# Motordrive.net
KiCad netlist of a schematic drawn in Altium Designer
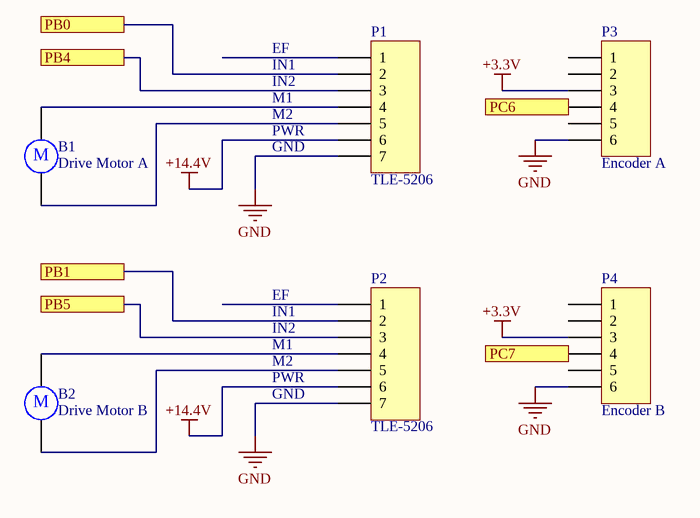
[diagram p0: Motordrive.SchDoc]

(export (version "E")
  (design (tool "Eeschema 10.0.6"))
  (components
    (comp (ref "B1")
      (value "Drive Motor A")
      (footprint "RB5-10.5")
      (description "Motor, General Kind")
      (fields (field (name "MANUFACTURER") "Generic Components"))
      (libsource (lib "ME218_BaseLib") (part "Motor"))
    )
    (comp (ref "B2")
      (value "Drive Motor B")
      (footprint "RB5-10.5")
      (description "Motor, General Kind")
      (fields (field (name "MANUFACTURER") "Generic Components"))
      (libsource (lib "ME218_BaseLib") (part "Motor"))
    )
    (comp (ref "P1")
      (value "TLE-5206")
      (footprint "HDR1X7")
      (description "Header, 7-Pin")
      (fields (field (name "PUBLISHER") "Altium Limited"))
      (libsource (lib "Miscellaneous Connectors") (part "Header 7"))
    )
    (comp (ref "P2")
      (value "TLE-5206")
      (footprint "HDR1X7")
      (description "Header, 7-Pin")
      (fields (field (name "PUBLISHER") "Altium Limited"))
      (libsource (lib "Miscellaneous Connectors") (part "Header 7"))
    )
    (comp (ref "P3")
      (value "Encoder A")
      (footprint "HDR1X6")
      (description "Header, 6-Pin")
      (fields (field (name "PUBLISHER") "Altium Limited"))
      (libsource (lib "Miscellaneous Connectors") (part "Header 6"))
    )
    (comp (ref "P4")
      (value "Encoder B")
      (footprint "HDR1X6")
      (description "Header, 6-Pin")
      (fields (field (name "PUBLISHER") "Altium Limited"))
      (libsource (lib "Miscellaneous Connectors") (part "Header 6"))
    )
  )
  (nets
    (net (code "1") (name "+3.3V") (class "Default")
      (node (ref "P3") (pin "3") (pinfunction "3_3") (pintype "passive"))
      (node (ref "P4") (pin "3") (pinfunction "3_3") (pintype "passive"))
    )
    (net (code "2") (name "+14.4V") (class "Default")
      (node (ref "P1") (pin "6") (pinfunction "6_6") (pintype "passive"))
      (node (ref "P2") (pin "6") (pinfunction "6_6") (pintype "passive"))
    )
    (net (code "3") (name "/PB0") (class "Default")
      (node (ref "P1") (pin "2") (pinfunction "2_2") (pintype "passive"))
    )
    (net (code "4") (name "/PB1") (class "Default")
      (node (ref "P2") (pin "2") (pinfunction "2_2") (pintype "passive"))
    )
    (net (code "5") (name "/PB4") (class "Default")
      (node (ref "P1") (pin "3") (pinfunction "3_3") (pintype "passive"))
    )
    (net (code "6") (name "/PB5") (class "Default")
      (node (ref "P2") (pin "3") (pinfunction "3_3") (pintype "passive"))
    )
    (net (code "7") (name "/PC6") (class "Default")
      (node (ref "P3") (pin "4") (pinfunction "4_4") (pintype "passive"))
    )
    (net (code "8") (name "/PC7") (class "Default")
      (node (ref "P4") (pin "4") (pinfunction "4_4") (pintype "passive"))
    )
    (net (code "9") (name "GND") (class "Default")
      (node (ref "P1") (pin "7") (pinfunction "7_7") (pintype "passive"))
      (node (ref "P2") (pin "7") (pinfunction "7_7") (pintype "passive"))
      (node (ref "P3") (pin "6") (pinfunction "6_6") (pintype "passive"))
      (node (ref "P4") (pin "6") (pinfunction "6_6") (pintype "passive"))
    )
    (net (code "10") (name "Net-(B1-Pad1)") (class "Default")
      (node (ref "B1") (pin "1") (pinfunction "1_1") (pintype "passive"))
      (node (ref "P1") (pin "4") (pinfunction "4_4") (pintype "passive"))
    )
    (net (code "11") (name "Net-(B1-Pad2)") (class "Default")
      (node (ref "B1") (pin "2") (pinfunction "2_2") (pintype "passive"))
      (node (ref "P1") (pin "5") (pinfunction "5_5") (pintype "passive"))
    )
    (net (code "12") (name "Net-(B2-Pad1)") (class "Default")
      (node (ref "B2") (pin "1") (pinfunction "1_1") (pintype "passive"))
      (node (ref "P2") (pin "4") (pinfunction "4_4") (pintype "passive"))
    )
    (net (code "13") (name "Net-(B2-Pad2)") (class "Default")
      (node (ref "B2") (pin "2") (pinfunction "2_2") (pintype "passive"))
      (node (ref "P2") (pin "5") (pinfunction "5_5") (pintype "passive"))
    )
    (net (code "14") (name "unconnected-(P1-Pad1)") (class "Default")
      (node (ref "P1") (pin "1") (pinfunction "1_1") (pintype "passive"))
    )
    (net (code "15") (name "unconnected-(P2-Pad1)") (class "Default")
      (node (ref "P2") (pin "1") (pinfunction "1_1") (pintype "passive"))
    )
    (net (code "16") (name "unconnected-(P3-Pad1)") (class "Default")
      (node (ref "P3") (pin "1") (pinfunction "1_1") (pintype "passive"))
    )
    (net (code "17") (name "unconnected-(P3-Pad2)") (class "Default")
      (node (ref "P3") (pin "2") (pinfunction "2_2") (pintype "passive"))
    )
    (net (code "18") (name "unconnected-(P3-Pad5)") (class "Default")
      (node (ref "P3") (pin "5") (pinfunction "5_5") (pintype "passive"))
    )
    (net (code "19") (name "unconnected-(P4-Pad1)") (class "Default")
      (node (ref "P4") (pin "1") (pinfunction "1_1") (pintype "passive"))
    )
    (net (code "20") (name "unconnected-(P4-Pad2)") (class "Default")
      (node (ref "P4") (pin "2") (pinfunction "2_2") (pintype "passive"))
    )
    (net (code "21") (name "unconnected-(P4-Pad5)") (class "Default")
      (node (ref "P4") (pin "5") (pinfunction "5_5") (pintype "passive"))
    )
  )
)
